# humidity_sensor_parts.net
KiCad netlist of a schematic drawn in EAGLE
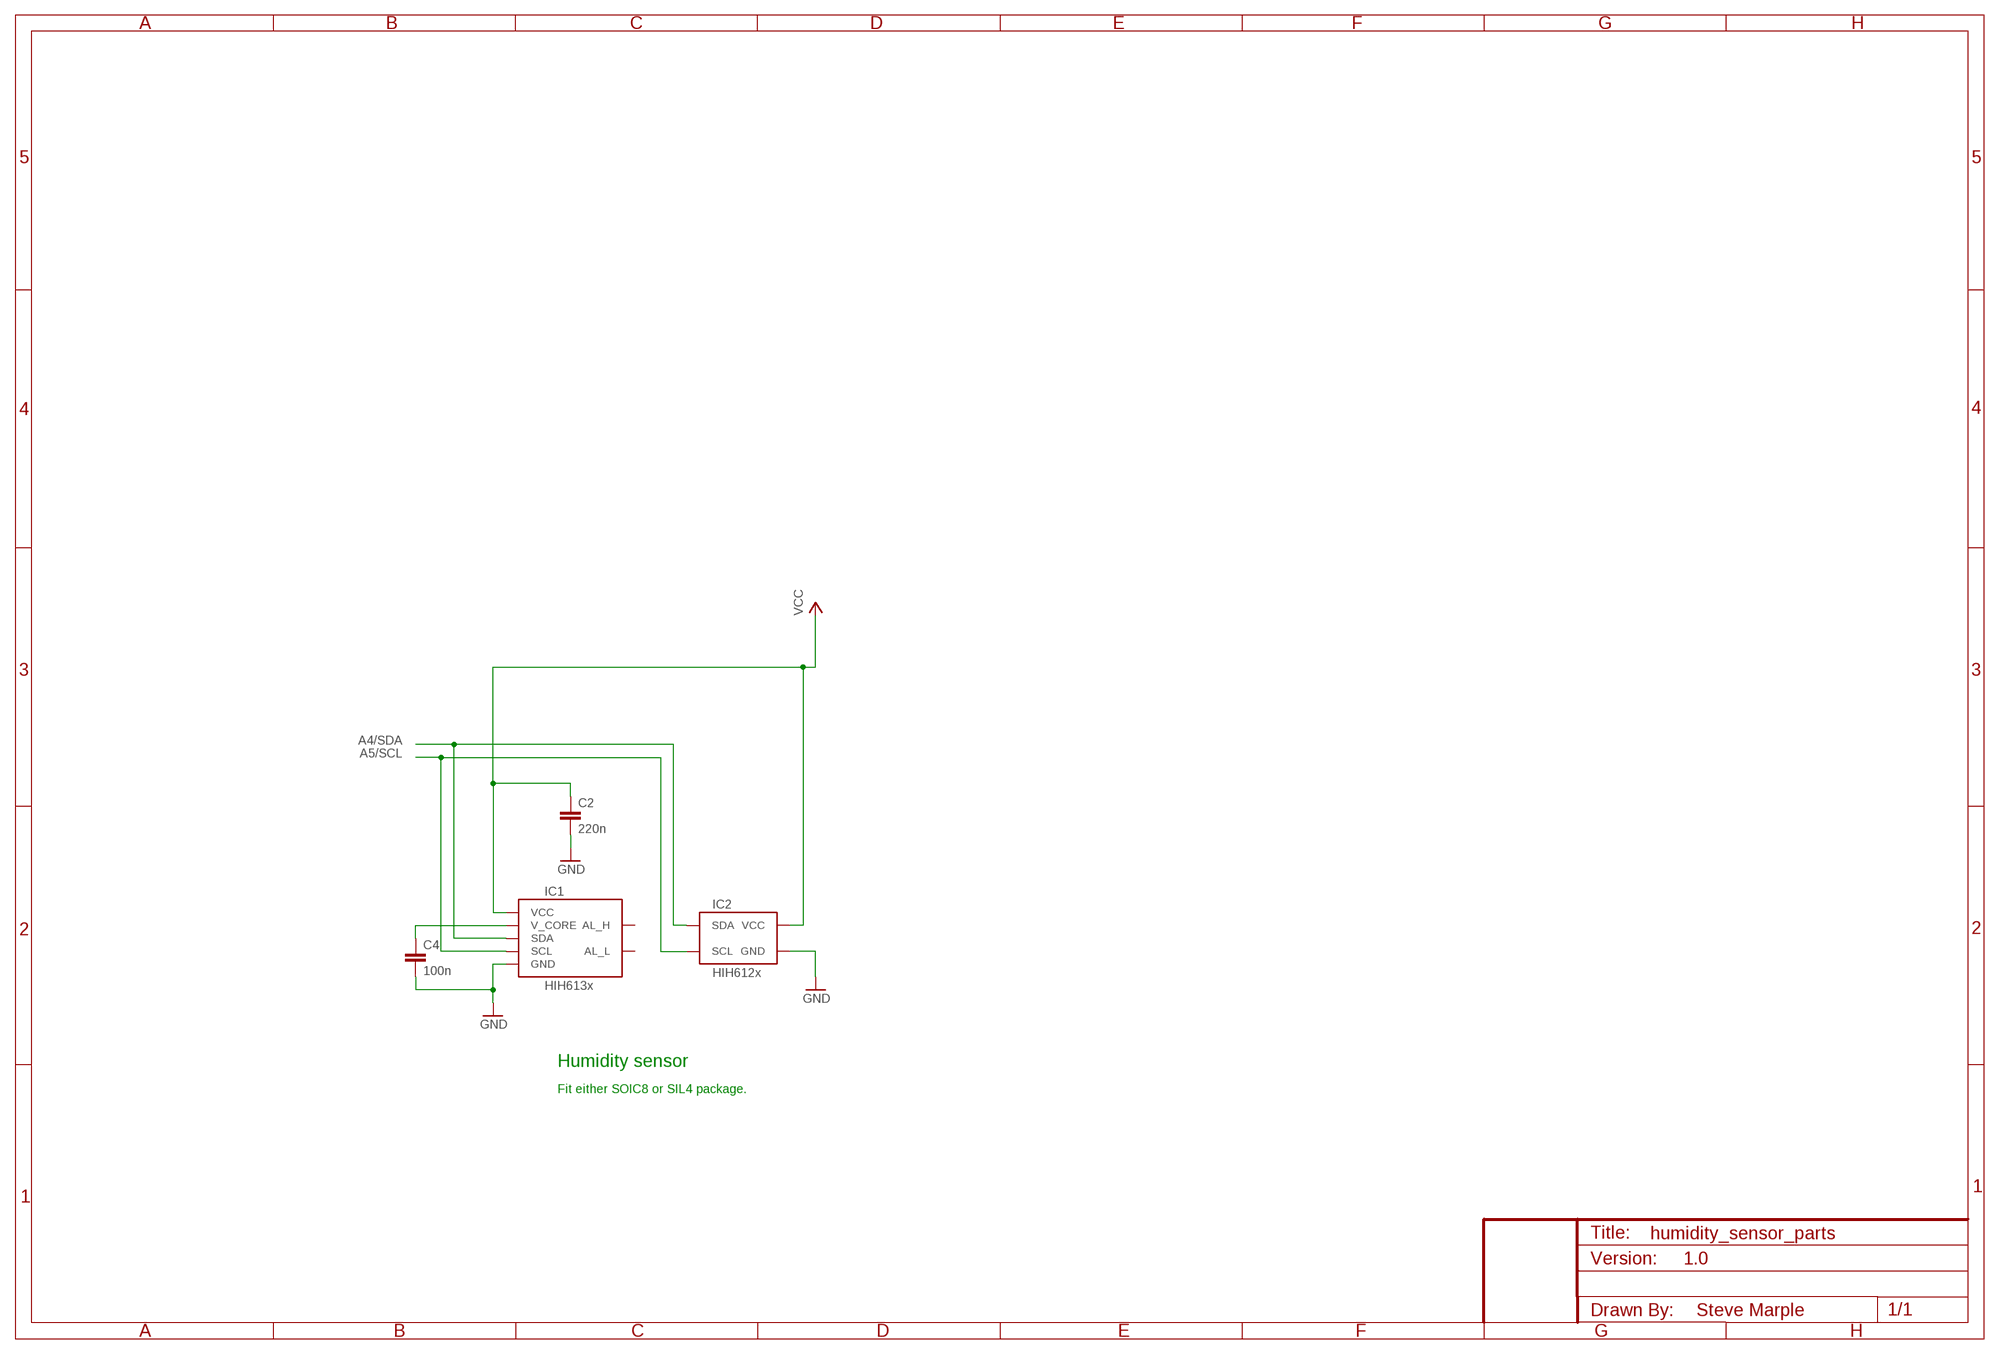
[diagram p0: schematic, sheet 1]

(export (version "E")
  (design (tool "Eeschema 10.0.6"))
  (components
    (comp (ref "C2")
      (value "220n")
      (footprint "eagle-import:CAP-PTH-SMALL")
      (libsource (lib "eagle-import") (part "CAPPTH"))
    )
    (comp (ref "C4")
      (value "100n")
      (footprint "eagle-import:CAP-PTH-SMALL")
      (libsource (lib "eagle-import") (part "CAPPTH"))
    )
    (comp (ref "IC1")
      (value "HIH613x")
      (footprint "eagle-import:SO08")
      (libsource (lib "eagle-import") (part "HONEYWELL-HIH613XSOIC8"))
    )
    (comp (ref "IC2")
      (value "HIH612x")
      (footprint "eagle-import:SIL04")
      (libsource (lib "eagle-import") (part "HONEYWELL-HIH612X"))
    )
  )
  (nets
    (net (code "1") (name "/A4{slash}SDA") (class "Default")
      (node (ref "IC1") (pin "4") (pinfunction "SDA_4") (pintype "bidirectional"))
      (node (ref "IC2") (pin "4") (pinfunction "SDA_4") (pintype "bidirectional"))
    )
    (net (code "2") (name "/A5{slash}SCL") (class "Default")
      (node (ref "IC1") (pin "3") (pinfunction "SCL_3") (pintype "bidirectional"))
      (node (ref "IC2") (pin "3") (pinfunction "SCL_3") (pintype "bidirectional"))
    )
    (net (code "3") (name "GND") (class "Default")
      (node (ref "C2") (pin "2") (pinfunction "2_2") (pintype "passive"))
      (node (ref "C4") (pin "2") (pinfunction "2_2") (pintype "passive"))
      (node (ref "IC1") (pin "2") (pinfunction "GND_2") (pintype "power_in"))
      (node (ref "IC2") (pin "2") (pinfunction "GND_2") (pintype "power_in"))
    )
    (net (code "4") (name "Net-(IC1-V_CORE)") (class "Default")
      (node (ref "C4") (pin "1") (pinfunction "1_1") (pintype "passive"))
      (node (ref "IC1") (pin "1") (pinfunction "V_CORE_1") (pintype "output"))
    )
    (net (code "5") (name "VCC") (class "Default")
      (node (ref "C2") (pin "1") (pinfunction "1_1") (pintype "passive"))
      (node (ref "IC1") (pin "8") (pinfunction "VCC_8") (pintype "power_in"))
      (node (ref "IC2") (pin "1") (pinfunction "VCC_1") (pintype "power_in"))
    )
    (net (code "6") (name "unconnected-(IC1-AL_H-Pad5)") (class "Default")
      (node (ref "IC1") (pin "5") (pinfunction "AL_H_5") (pintype "bidirectional"))
    )
    (net (code "7") (name "unconnected-(IC1-AL_L-Pad6)") (class "Default")
      (node (ref "IC1") (pin "6") (pinfunction "AL_L_6") (pintype "bidirectional"))
    )
  )
)
